# mosquino-power-rf.net
KiCad netlist of a schematic drawn in EAGLE
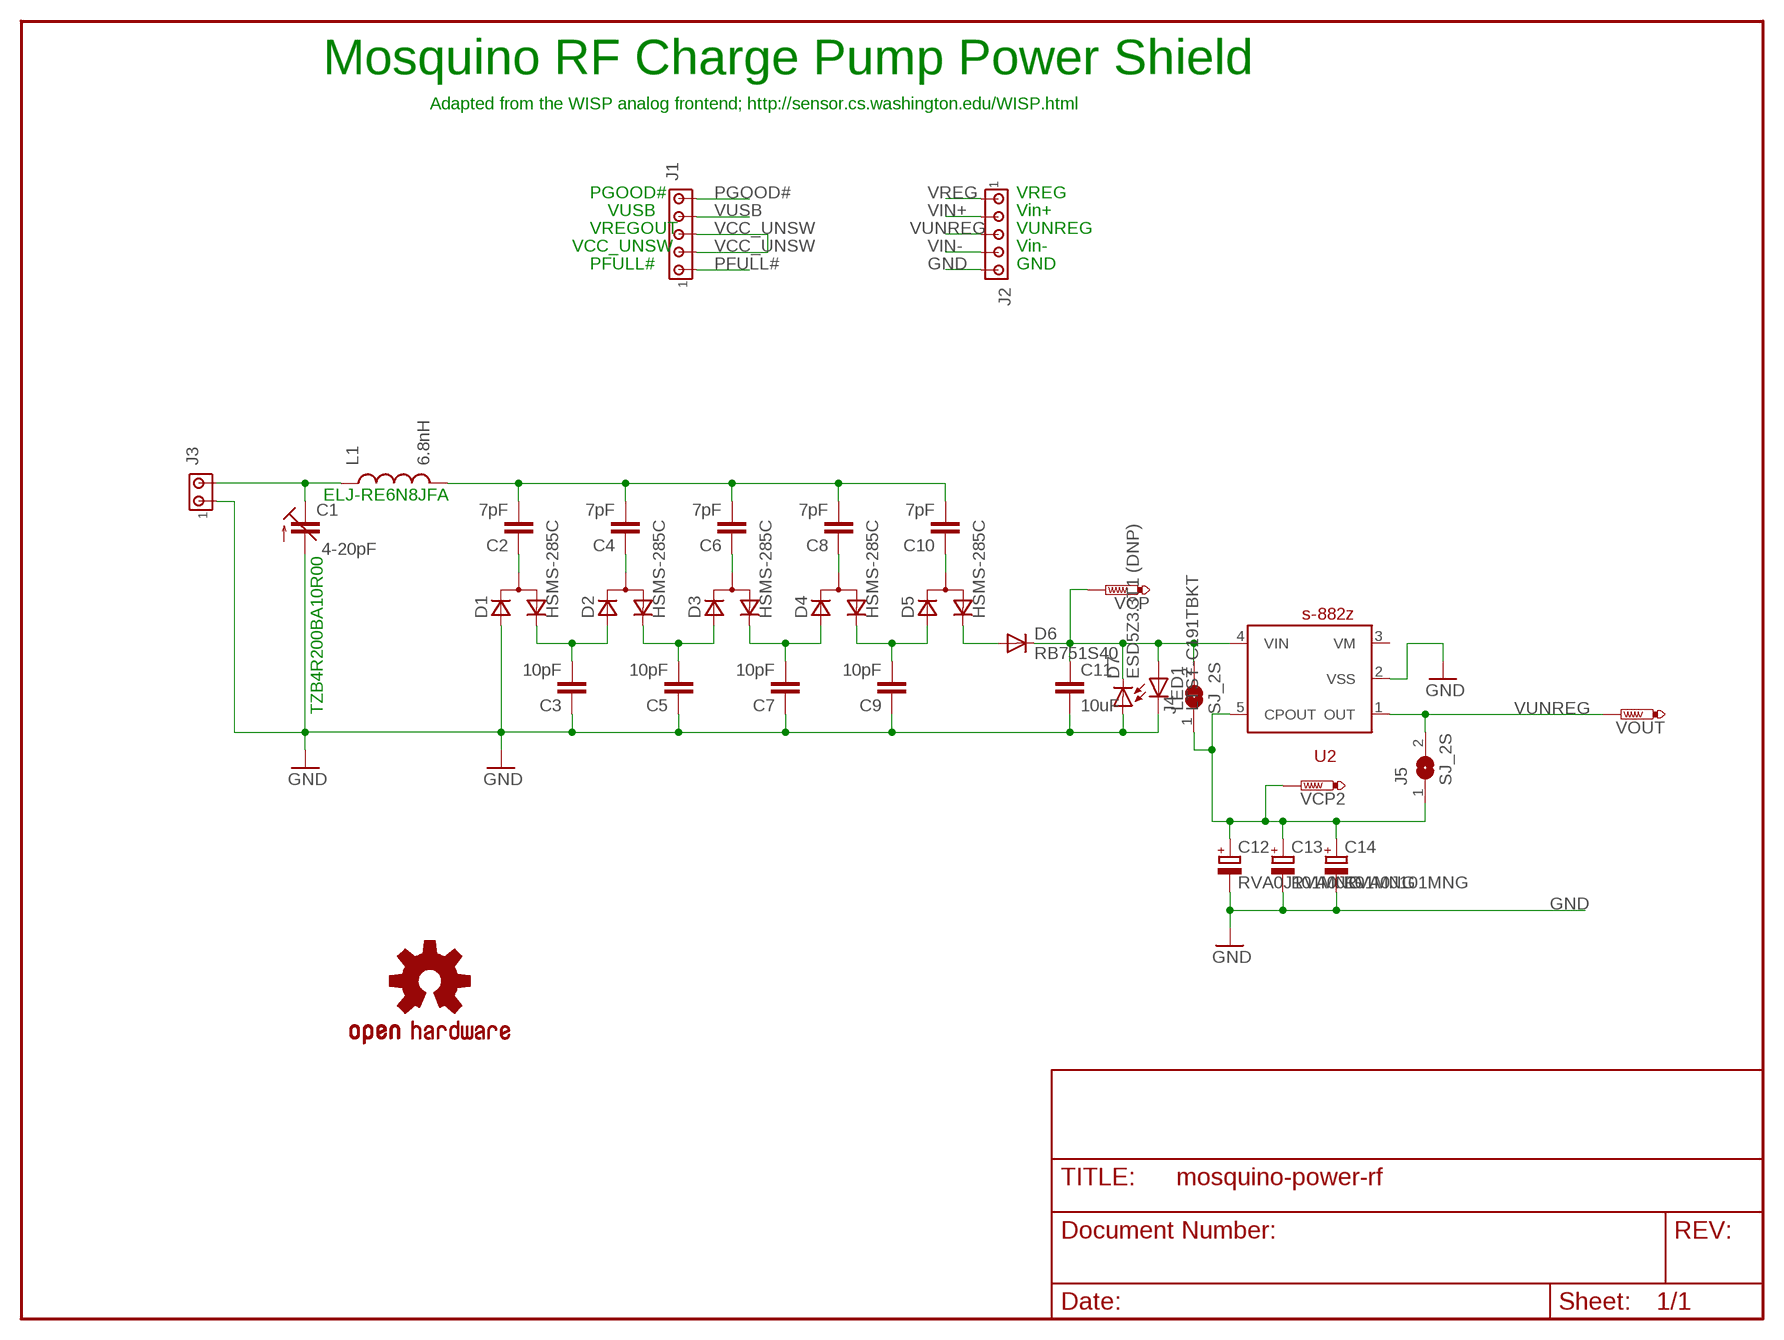
[diagram p0: schematic, sheet 1]

(export (version "E")
  (design (tool "Eeschema 10.0.6"))
  (components
    (comp (ref "C1")
      (value "4-20pF")
      (footprint "eagle-import:CTRIM3018_12")
      (libsource (lib "eagle-import") (part "C-TRIMM3018_12"))
    )
    (comp (ref "C2")
      (value "7pF")
      (footprint "eagle-import:C0603")
      (libsource (lib "eagle-import") (part "C-EUC0603"))
    )
    (comp (ref "C3")
      (value "10pF")
      (footprint "eagle-import:C0603")
      (libsource (lib "eagle-import") (part "C-EUC0603"))
    )
    (comp (ref "C4")
      (value "7pF")
      (footprint "eagle-import:C0603")
      (libsource (lib "eagle-import") (part "C-EUC0603"))
    )
    (comp (ref "C5")
      (value "10pF")
      (footprint "eagle-import:C0603")
      (libsource (lib "eagle-import") (part "C-EUC0603"))
    )
    (comp (ref "C6")
      (value "7pF")
      (footprint "eagle-import:C0603")
      (libsource (lib "eagle-import") (part "C-EUC0603"))
    )
    (comp (ref "C7")
      (value "10pF")
      (footprint "eagle-import:C0603")
      (libsource (lib "eagle-import") (part "C-EUC0603"))
    )
    (comp (ref "C8")
      (value "7pF")
      (footprint "eagle-import:C0603")
      (libsource (lib "eagle-import") (part "C-EUC0603"))
    )
    (comp (ref "C9")
      (value "10pF")
      (footprint "eagle-import:C0603")
      (libsource (lib "eagle-import") (part "C-EUC0603"))
    )
    (comp (ref "C10")
      (value "7pF")
      (footprint "eagle-import:C0603")
      (libsource (lib "eagle-import") (part "C-EUC0603"))
    )
    (comp (ref "C11")
      (value "10uF")
      (footprint "eagle-import:C0805")
      (libsource (lib "eagle-import") (part "C-EUC0805"))
    )
    (comp (ref "C12")
      (value "RVA0J101MNG")
      (footprint "eagle-import:CASE_D")
      (libsource (lib "eagle-import") (part "CAP_TANT_D"))
    )
    (comp (ref "C13")
      (value "RVA0J101MNG")
      (footprint "eagle-import:CASE_D")
      (libsource (lib "eagle-import") (part "CAP_TANT_D"))
    )
    (comp (ref "C14")
      (value "RVA0J101MNG")
      (footprint "eagle-import:CASE_D")
      (libsource (lib "eagle-import") (part "CAP_TANT_D"))
    )
    (comp (ref "D1")
      (value "HSMS-285C")
      (footprint "eagle-import:SOT-323")
      (libsource (lib "eagle-import") (part "DIODE_DUAL_ACACSOT323"))
    )
    (comp (ref "D2")
      (value "HSMS-285C")
      (footprint "eagle-import:SOT-323")
      (libsource (lib "eagle-import") (part "DIODE_DUAL_ACACSOT323"))
    )
    (comp (ref "D3")
      (value "HSMS-285C")
      (footprint "eagle-import:SOT-323")
      (libsource (lib "eagle-import") (part "DIODE_DUAL_ACACSOT323"))
    )
    (comp (ref "D4")
      (value "HSMS-285C")
      (footprint "eagle-import:SOT-323")
      (libsource (lib "eagle-import") (part "DIODE_DUAL_ACACSOT323"))
    )
    (comp (ref "D5")
      (value "HSMS-285C")
      (footprint "eagle-import:SOT-323")
      (libsource (lib "eagle-import") (part "DIODE_DUAL_ACACSOT323"))
    )
    (comp (ref "D6")
      (value "RB751S40")
      (footprint "eagle-import:SOD523")
      (libsource (lib "eagle-import") (part "DIODE-SOD523"))
    )
    (comp (ref "D7")
      (value "ESD5Z3.3T1 (DNP)")
      (footprint "eagle-import:SOD523")
      (libsource (lib "eagle-import") (part "DIODE-SOD523"))
    )
    (comp (ref "J1")
      (value "MTA05-100")
      (footprint "eagle-import:10X05MTA")
      (libsource (lib "eagle-import") (part "MTA05-100"))
    )
    (comp (ref "J2")
      (value "MTA05-100")
      (footprint "eagle-import:10X05MTA")
      (libsource (lib "eagle-import") (part "MTA05-100"))
    )
    (comp (ref "J3")
      (value "MTA02-100")
      (footprint "eagle-import:10X02MTA")
      (libsource (lib "eagle-import") (part "MTA02-100"))
    )
    (comp (ref "J4")
      (value "SJ_2S")
      (footprint "eagle-import:SJ2_S")
      (libsource (lib "eagle-import") (part "SJ_2S"))
    )
    (comp (ref "J5")
      (value "SJ_2S")
      (footprint "eagle-import:SJ2_S")
      (libsource (lib "eagle-import") (part "SJ_2S"))
    )
    (comp (ref "L1")
      (value "6.8nH")
      (footprint "eagle-import:0603")
      (libsource (lib "eagle-import") (part "INDUCTOR0603"))
    )
    (comp (ref "LED1")
      (value "LTST-C191TBKT")
      (footprint "eagle-import:CHIP-LED0603")
      (libsource (lib "eagle-import") (part "LEDCHIP-LED0603"))
    )
    (comp (ref "LOGO1")
      (value "OSHW-LOGOS")
      (footprint "eagle-import:OSHW-LOGO-S")
      (libsource (lib "eagle-import") (part "OSHW-LOGOS"))
    )
    (comp (ref "U2")
      (value "s-882z")
      (footprint "eagle-import:SOT23-5")
      (libsource (lib "eagle-import") (part "S-882Z"))
    )
    (comp (ref "VCP")
      (value "PTR1PAD1-13")
      (footprint "eagle-import:P1-13")
      (libsource (lib "eagle-import") (part "PTR1PAD1-13"))
    )
    (comp (ref "VCP2")
      (value "PTR1PAD1-13")
      (footprint "eagle-import:P1-13")
      (libsource (lib "eagle-import") (part "PTR1PAD1-13"))
    )
    (comp (ref "VOUT")
      (value "PTR1PAD1-13")
      (footprint "eagle-import:P1-13")
      (libsource (lib "eagle-import") (part "PTR1PAD1-13"))
    )
  )
  (nets
    (net (code "1") (name "/PFULL#") (class "Default")
      (node (ref "J1") (pin "1") (pinfunction "1_1") (pintype "passive"))
    )
    (net (code "2") (name "/PGOOD#") (class "Default")
      (node (ref "J1") (pin "5") (pinfunction "5_5") (pintype "passive"))
    )
    (net (code "3") (name "/VCC_UNSW") (class "Default")
      (node (ref "J1") (pin "2") (pinfunction "2_2") (pintype "passive"))
      (node (ref "J1") (pin "3") (pinfunction "3_3") (pintype "passive"))
    )
    (net (code "4") (name "/VIN+") (class "Default")
      (node (ref "J2") (pin "2") (pinfunction "2_2") (pintype "passive"))
    )
    (net (code "5") (name "/VIN-") (class "Default")
      (node (ref "J2") (pin "4") (pinfunction "4_4") (pintype "passive"))
    )
    (net (code "6") (name "/VREG") (class "Default")
      (node (ref "J2") (pin "1") (pinfunction "1_1") (pintype "passive"))
    )
    (net (code "7") (name "/VUNREG") (class "Default")
      (node (ref "J2") (pin "3") (pinfunction "3_3") (pintype "passive"))
      (node (ref "J5") (pin "2") (pinfunction "2_2") (pintype "passive"))
      (node (ref "U2") (pin "1") (pinfunction "OUT_1") (pintype "bidirectional"))
      (node (ref "VOUT") (pin "TP") (pinfunction "TP_TP") (pintype "input"))
    )
    (net (code "8") (name "/VUSB") (class "Default")
      (node (ref "J1") (pin "4") (pinfunction "4_4") (pintype "passive"))
    )
    (net (code "9") (name "GND") (class "Default")
      (node (ref "C1") (pin "-") (pinfunction "A_-") (pintype "passive"))
      (node (ref "C11") (pin "2") (pinfunction "2_2") (pintype "passive"))
      (node (ref "C12") (pin "2") (pinfunction "-_2") (pintype "passive"))
      (node (ref "C13") (pin "2") (pinfunction "-_2") (pintype "passive"))
      (node (ref "C14") (pin "2") (pinfunction "-_2") (pintype "passive"))
      (node (ref "C3") (pin "1") (pinfunction "1_1") (pintype "passive"))
      (node (ref "C5") (pin "1") (pinfunction "1_1") (pintype "passive"))
      (node (ref "C7") (pin "1") (pinfunction "1_1") (pintype "passive"))
      (node (ref "C9") (pin "1") (pinfunction "1_1") (pintype "passive"))
      (node (ref "D1") (pin "1") (pinfunction "A_1") (pintype "passive"))
      (node (ref "D7") (pin "A") (pinfunction "A_A") (pintype "passive"))
      (node (ref "J2") (pin "5") (pinfunction "5_5") (pintype "passive"))
      (node (ref "J3") (pin "1") (pinfunction "1_1") (pintype "passive"))
      (node (ref "LED1") (pin "C") (pinfunction "C_C") (pintype "passive"))
      (node (ref "U2") (pin "2") (pinfunction "VSS_2") (pintype "bidirectional"))
    )
    (net (code "10") (name "Net-(C1-E)") (class "Default")
      (node (ref "C1") (pin "+") (pinfunction "E_+") (pintype "passive"))
      (node (ref "J3") (pin "2") (pinfunction "2_2") (pintype "passive"))
      (node (ref "L1") (pin "1") (pinfunction "1_1") (pintype "passive"))
    )
    (net (code "11") (name "Net-(C10-Pad2)") (class "Default")
      (node (ref "C10") (pin "2") (pinfunction "2_2") (pintype "passive"))
      (node (ref "C2") (pin "2") (pinfunction "2_2") (pintype "passive"))
      (node (ref "C4") (pin "2") (pinfunction "2_2") (pintype "passive"))
      (node (ref "C6") (pin "2") (pinfunction "2_2") (pintype "passive"))
      (node (ref "C8") (pin "2") (pinfunction "2_2") (pintype "passive"))
      (node (ref "L1") (pin "2") (pinfunction "2_2") (pintype "passive"))
    )
    (net (code "12") (name "Net-(C12-+)") (class "Default")
      (node (ref "C12") (pin "1") (pinfunction "+_1") (pintype "passive"))
      (node (ref "C13") (pin "1") (pinfunction "+_1") (pintype "passive"))
      (node (ref "C14") (pin "1") (pinfunction "+_1") (pintype "passive"))
      (node (ref "J4") (pin "1") (pinfunction "1_1") (pintype "passive"))
      (node (ref "J5") (pin "1") (pinfunction "1_1") (pintype "passive"))
      (node (ref "U2") (pin "5") (pinfunction "CPOUT_5") (pintype "bidirectional"))
      (node (ref "VCP2") (pin "TP") (pinfunction "TP_TP") (pintype "input"))
    )
    (net (code "13") (name "Net-(D1-C)") (class "Default")
      (node (ref "C3") (pin "2") (pinfunction "2_2") (pintype "passive"))
      (node (ref "D1") (pin "2") (pinfunction "C_2") (pintype "passive"))
      (node (ref "D2") (pin "1") (pinfunction "A_1") (pintype "passive"))
    )
    (net (code "14") (name "Net-(D1-CA)") (class "Default")
      (node (ref "C2") (pin "1") (pinfunction "1_1") (pintype "passive"))
      (node (ref "D1") (pin "3") (pinfunction "CA_3") (pintype "passive"))
    )
    (net (code "15") (name "Net-(D2-C)") (class "Default")
      (node (ref "C5") (pin "2") (pinfunction "2_2") (pintype "passive"))
      (node (ref "D2") (pin "2") (pinfunction "C_2") (pintype "passive"))
      (node (ref "D3") (pin "1") (pinfunction "A_1") (pintype "passive"))
    )
    (net (code "16") (name "Net-(D2-CA)") (class "Default")
      (node (ref "C4") (pin "1") (pinfunction "1_1") (pintype "passive"))
      (node (ref "D2") (pin "3") (pinfunction "CA_3") (pintype "passive"))
    )
    (net (code "17") (name "Net-(D3-C)") (class "Default")
      (node (ref "C7") (pin "2") (pinfunction "2_2") (pintype "passive"))
      (node (ref "D3") (pin "2") (pinfunction "C_2") (pintype "passive"))
      (node (ref "D4") (pin "1") (pinfunction "A_1") (pintype "passive"))
    )
    (net (code "18") (name "Net-(D3-CA)") (class "Default")
      (node (ref "C6") (pin "1") (pinfunction "1_1") (pintype "passive"))
      (node (ref "D3") (pin "3") (pinfunction "CA_3") (pintype "passive"))
    )
    (net (code "19") (name "Net-(D4-C)") (class "Default")
      (node (ref "C9") (pin "2") (pinfunction "2_2") (pintype "passive"))
      (node (ref "D4") (pin "2") (pinfunction "C_2") (pintype "passive"))
      (node (ref "D5") (pin "1") (pinfunction "A_1") (pintype "passive"))
    )
    (net (code "20") (name "Net-(D4-CA)") (class "Default")
      (node (ref "C8") (pin "1") (pinfunction "1_1") (pintype "passive"))
      (node (ref "D4") (pin "3") (pinfunction "CA_3") (pintype "passive"))
    )
    (net (code "21") (name "Net-(D5-C)") (class "Default")
      (node (ref "D5") (pin "2") (pinfunction "C_2") (pintype "passive"))
      (node (ref "D6") (pin "A") (pinfunction "A_A") (pintype "passive"))
    )
    (net (code "22") (name "Net-(D5-CA)") (class "Default")
      (node (ref "C10") (pin "1") (pinfunction "1_1") (pintype "passive"))
      (node (ref "D5") (pin "3") (pinfunction "CA_3") (pintype "passive"))
    )
    (net (code "23") (name "Net-(U2-VIN)") (class "Default")
      (node (ref "C11") (pin "1") (pinfunction "1_1") (pintype "passive"))
      (node (ref "D6") (pin "C") (pinfunction "C_C") (pintype "passive"))
      (node (ref "D7") (pin "C") (pinfunction "C_C") (pintype "passive"))
      (node (ref "J4") (pin "2") (pinfunction "2_2") (pintype "passive"))
      (node (ref "LED1") (pin "A") (pinfunction "A_A") (pintype "passive"))
      (node (ref "U2") (pin "4") (pinfunction "VIN_4") (pintype "bidirectional"))
      (node (ref "VCP") (pin "TP") (pinfunction "TP_TP") (pintype "input"))
    )
    (net (code "24") (name "unconnected-(U2-VM-Pad3)") (class "Default")
      (node (ref "U2") (pin "3") (pinfunction "VM_3") (pintype "bidirectional"))
    )
  )
)
